# fm_receiver_schematic.net
KiCad netlist of a schematic drawn in EAGLE
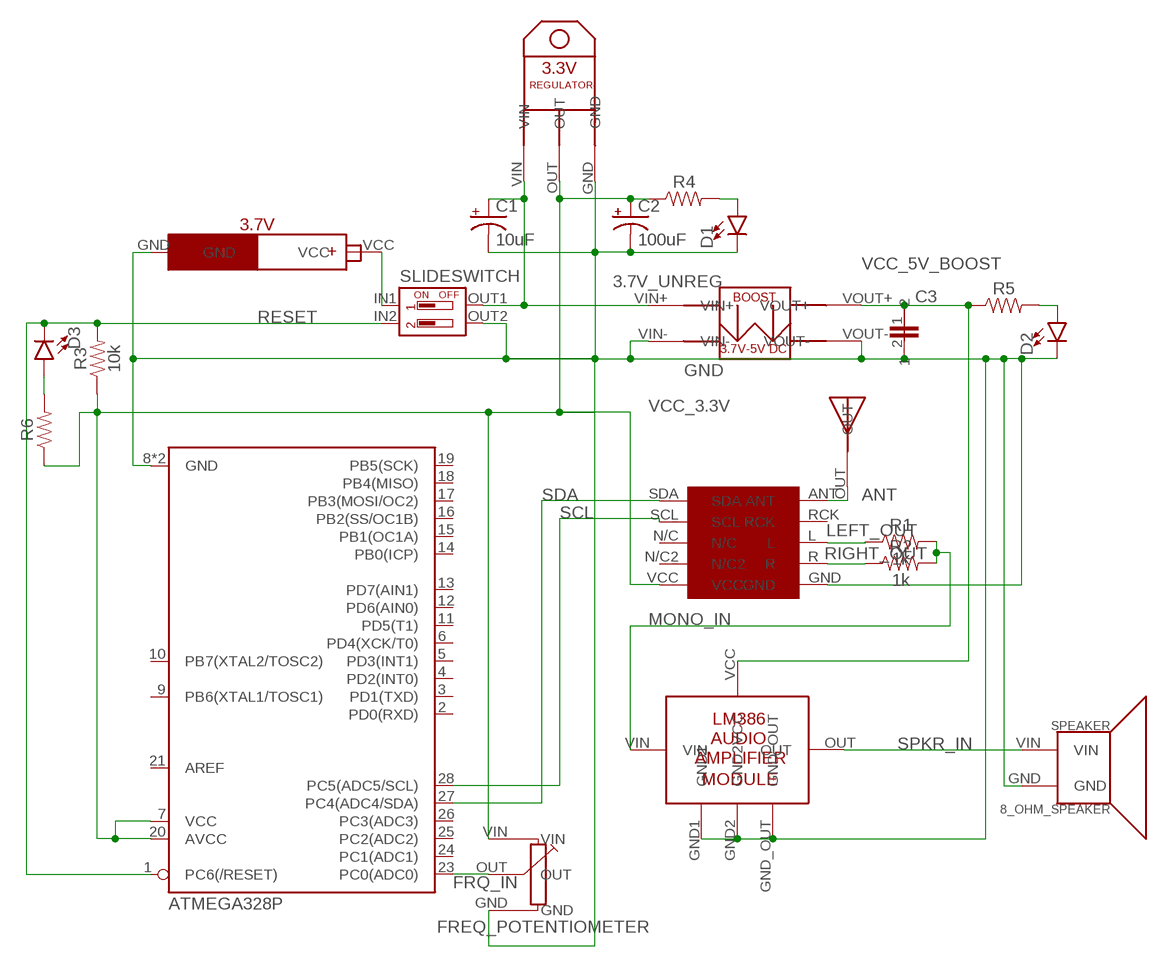
[diagram p0: schematic, sheet 1]

(export (version "E")
  (design (tool "Eeschema 10.0.6"))
  (components
    (comp (ref "3.3V_REGULATOR")
      (value "LDO_REG_3.3V")
      (footprint "eagle-import:LDO_REG_3.3V")
      (libsource (lib "eagle-import") (part "LDO_REG_3.3V"))
    )
    (comp (ref "3.7_5_BOOST")
      (value "3.7V_5V_BOOST_CONV")
      (footprint "eagle-import:3.7V_5V_BOOST_CONV")
      (libsource (lib "eagle-import") (part "3.7V_5V_BOOST_CONV"))
    )
    (comp (ref "ANTENNA")
      (value "SIMPLE_ANTENNA")
      (footprint "eagle-import:SIMPLE_ANTENNA")
      (libsource (lib "eagle-import") (part "SIMPLE_ANTENNA"))
    )
    (comp (ref "ATMEGA328P")
      (value "328P")
      (footprint "eagle-import:DIP28")
      (libsource (lib "eagle-import") (part "ATMEGA328P_PDIP"))
    )
    (comp (ref "C1")
      (value "10uF")
      (footprint "eagle-import:CPOL-RADIAL-2.5MM-5MM")
      (libsource (lib "eagle-import") (part "10UF-POLAR-RADIAL-2.5MM-25V-20%"))
    )
    (comp (ref "C2")
      (value "100uF")
      (footprint "eagle-import:CPOL-RADIAL-2.5MM-6.5MM")
      (libsource (lib "eagle-import") (part "100UF-POLAR-RADIAL-2.5MM-25V-20%"))
    )
    (comp (ref "C3")
      (value "0.1UF_CER_CAP")
      (footprint "eagle-import:0.1UF_CER_CAP")
      (libsource (lib "eagle-import") (part "0.1UF_CER_CAP"))
    )
    (comp (ref "D1")
      (value "LED5MM")
      (footprint "eagle-import:LED_5MM")
      (libsource (lib "eagle-import") (part "LED5MM"))
    )
    (comp (ref "D2")
      (value "LED5MM")
      (footprint "eagle-import:LED_5MM")
      (libsource (lib "eagle-import") (part "LED5MM"))
    )
    (comp (ref "D3")
      (value "LED5MM")
      (footprint "eagle-import:LED_5MM")
      (libsource (lib "eagle-import") (part "LED5MM"))
    )
    (comp (ref "FM_RECEIVER")
      (value "RDA")
      (footprint "eagle-import:RDA")
      (libsource (lib "eagle-import") (part "RDA"))
    )
    (comp (ref "FREQ_POTENTIOMETER")
      (value "POTENTIOMETER_LARGE")
      (footprint "eagle-import:POTENTIOMETER_LARGE")
      (libsource (lib "eagle-import") (part "POTENTIOMETER_LARGE"))
    )
    (comp (ref "LM386_MODULE")
      (value "LM386_AUDIO_AMP_MODULE")
      (footprint "eagle-import:LM386_AUDIO_AMP_MODULE")
      (libsource (lib "eagle-import") (part "LM386_AUDIO_AMP_MODULE"))
    )
    (comp (ref "PWR_SUPPLY")
      (value "3.7V_PWR_DESIGNATOR")
      (footprint "eagle-import:3.7V_PWR_DESIGNATOR")
      (libsource (lib "eagle-import") (part "3.7V_PWR_DESIGNATOR"))
    )
    (comp (ref "R1")
      (value "1k")
      (footprint "eagle-import:AXIAL-0.3")
      (libsource (lib "eagle-import") (part "1KOHM-HORIZ-1/4W-1%"))
    )
    (comp (ref "R2")
      (value "1k")
      (footprint "eagle-import:AXIAL-0.3")
      (libsource (lib "eagle-import") (part "1KOHM-HORIZ-1/4W-1%"))
    )
    (comp (ref "R3")
      (value "10k")
      (footprint "eagle-import:AXIAL-0.3")
      (libsource (lib "eagle-import") (part "10KOHM-HORIZ-1/4W-1%"))
    )
    (comp (ref "R4")
      (value "RESISTORAXIAL-0.3")
      (footprint "eagle-import:AXIAL-0.3")
      (libsource (lib "eagle-import") (part "RESISTORAXIAL-0.3"))
    )
    (comp (ref "R5")
      (value "RESISTORAXIAL-0.3")
      (footprint "eagle-import:AXIAL-0.3")
      (libsource (lib "eagle-import") (part "RESISTORAXIAL-0.3"))
    )
    (comp (ref "R6")
      (value "RESISTORAXIAL-0.3")
      (footprint "eagle-import:AXIAL-0.3")
      (libsource (lib "eagle-import") (part "RESISTORAXIAL-0.3"))
    )
    (comp (ref "SLIDESWITCH")
      (value "2_WAY_DIP_PWR_RST_SLIDESWITCH")
      (footprint "eagle-import:2_WAY_DIP_PWR_RST_SLIDESWITCH")
      (libsource (lib "eagle-import") (part "2_WAY_DIP_PWR_RST_SLIDESWITCH"))
    )
    (comp (ref "SPEAKER")
      (value "8_OHM_SPEAKER")
      (footprint "eagle-import:8_OHM_SPEAKER")
      (libsource (lib "eagle-import") (part "8_OHM_SPEAKER"))
    )
  )
  (nets
    (net (code "1") (name "/3.7V_UNREG") (class "Default")
      (node (ref "3.3V_REGULATOR") (pin "VIN") (pinfunction "VIN_VIN") (pintype "bidirectional"))
      (node (ref "3.7_5_BOOST") (pin "VIN+") (pinfunction "VIN+_VIN+") (pintype "bidirectional"))
      (node (ref "C1") (pin "1") (pinfunction "+_1") (pintype "passive"))
      (node (ref "SLIDESWITCH") (pin "OUT1") (pinfunction "OUT1_OUT1") (pintype "bidirectional"))
    )
    (net (code "2") (name "/ANT") (class "Default")
      (node (ref "ANTENNA") (pin "OUT") (pinfunction "OUT_OUT") (pintype "bidirectional"))
      (node (ref "FM_RECEIVER") (pin "ANT") (pinfunction "ANT_ANT") (pintype "input"))
    )
    (net (code "3") (name "/FRQ_IN") (class "Default")
      (node (ref "ATMEGA328P") (pin "23") (pinfunction "PC0(ADC0)_23") (pintype "bidirectional"))
      (node (ref "FREQ_POTENTIOMETER") (pin "OUT") (pinfunction "OUT_OUT") (pintype "bidirectional"))
    )
    (net (code "4") (name "/GND") (class "Default")
      (node (ref "3.3V_REGULATOR") (pin "GND") (pinfunction "GND_GND") (pintype "bidirectional"))
      (node (ref "3.7_5_BOOST") (pin "VIN-") (pinfunction "VIN-_VIN-") (pintype "bidirectional"))
      (node (ref "3.7_5_BOOST") (pin "VOUT-") (pinfunction "VOUT-_VOUT-") (pintype "bidirectional"))
      (node (ref "ATMEGA328P") (pin "22") (pinfunction "GND_22") (pintype "bidirectional"))
      (node (ref "ATMEGA328P") (pin "8") (pinfunction "GND_8") (pintype "bidirectional"))
      (node (ref "C1") (pin "2") (pinfunction "-_2") (pintype "passive"))
      (node (ref "C2") (pin "2") (pinfunction "-_2") (pintype "passive"))
      (node (ref "C3") (pin "2") (pinfunction "2_2") (pintype "bidirectional"))
      (node (ref "D1") (pin "K") (pinfunction "C_K") (pintype "passive"))
      (node (ref "D2") (pin "K") (pinfunction "C_K") (pintype "passive"))
      (node (ref "FM_RECEIVER") (pin "GND") (pinfunction "GND_GND") (pintype "power_in"))
      (node (ref "FREQ_POTENTIOMETER") (pin "GND") (pinfunction "GND_GND") (pintype "bidirectional"))
      (node (ref "LM386_MODULE") (pin "GND1") (pinfunction "GND1_GND1") (pintype "bidirectional"))
      (node (ref "LM386_MODULE") (pin "GND2") (pinfunction "GND2_GND2") (pintype "bidirectional"))
      (node (ref "LM386_MODULE") (pin "GND_OUT") (pinfunction "GND_OUT_GND_OUT") (pintype "bidirectional"))
      (node (ref "PWR_SUPPLY") (pin "GND") (pinfunction "GND_GND") (pintype "bidirectional"))
      (node (ref "SLIDESWITCH") (pin "OUT2") (pinfunction "OUT2_OUT2") (pintype "bidirectional"))
      (node (ref "SPEAKER") (pin "GND") (pinfunction "GND_GND") (pintype "bidirectional"))
    )
    (net (code "5") (name "/LEFT_OUT") (class "Default")
      (node (ref "FM_RECEIVER") (pin "L") (pinfunction "L_L") (pintype "output"))
      (node (ref "R1") (pin "P$1") (pinfunction "1_P$1") (pintype "passive"))
    )
    (net (code "6") (name "/MONO_IN") (class "Default")
      (node (ref "LM386_MODULE") (pin "VIN") (pinfunction "VIN_VIN") (pintype "bidirectional"))
      (node (ref "R1") (pin "P$2") (pinfunction "2_P$2") (pintype "passive"))
      (node (ref "R2") (pin "P$2") (pinfunction "2_P$2") (pintype "passive"))
    )
    (net (code "7") (name "/RESET") (class "Default")
      (node (ref "ATMEGA328P") (pin "1") (pinfunction "PC6(/RESET)_1") (pintype "bidirectional"))
      (node (ref "D3") (pin "K") (pinfunction "C_K") (pintype "passive"))
      (node (ref "R3") (pin "P$2") (pinfunction "2_P$2") (pintype "passive"))
      (node (ref "SLIDESWITCH") (pin "IN2") (pinfunction "IN2_IN2") (pintype "bidirectional"))
    )
    (net (code "8") (name "/RIGHT_OUT") (class "Default")
      (node (ref "FM_RECEIVER") (pin "R") (pinfunction "R_R") (pintype "output"))
      (node (ref "R2") (pin "P$1") (pinfunction "1_P$1") (pintype "passive"))
    )
    (net (code "9") (name "/SCL") (class "Default")
      (node (ref "ATMEGA328P") (pin "28") (pinfunction "PC5(ADC5/SCL)_28") (pintype "bidirectional"))
      (node (ref "FM_RECEIVER") (pin "SCL") (pinfunction "SCL_SCL") (pintype "bidirectional"))
    )
    (net (code "10") (name "/SDA") (class "Default")
      (node (ref "ATMEGA328P") (pin "27") (pinfunction "PC4(ADC4/SDA)_27") (pintype "bidirectional"))
      (node (ref "FM_RECEIVER") (pin "SDA") (pinfunction "SDA_SDA") (pintype "bidirectional"))
    )
    (net (code "11") (name "/SPKR_IN") (class "Default")
      (node (ref "LM386_MODULE") (pin "OUT") (pinfunction "OUT_OUT") (pintype "bidirectional"))
      (node (ref "SPEAKER") (pin "VIN") (pinfunction "VIN_VIN") (pintype "bidirectional"))
    )
    (net (code "12") (name "/VCC_3.3V") (class "Default")
      (node (ref "3.3V_REGULATOR") (pin "OUT") (pinfunction "OUT_OUT") (pintype "bidirectional"))
      (node (ref "ATMEGA328P") (pin "20") (pinfunction "AVCC_20") (pintype "bidirectional"))
      (node (ref "ATMEGA328P") (pin "7") (pinfunction "VCC_7") (pintype "bidirectional"))
      (node (ref "C2") (pin "1") (pinfunction "+_1") (pintype "passive"))
      (node (ref "FM_RECEIVER") (pin "VCC") (pinfunction "VCC_VCC") (pintype "power_in"))
      (node (ref "FREQ_POTENTIOMETER") (pin "VIN") (pinfunction "VIN_VIN") (pintype "bidirectional"))
      (node (ref "R3") (pin "P$1") (pinfunction "1_P$1") (pintype "passive"))
      (node (ref "R4") (pin "P$1") (pinfunction "1_P$1") (pintype "passive"))
      (node (ref "R6") (pin "P$1") (pinfunction "1_P$1") (pintype "passive"))
    )
    (net (code "13") (name "/VCC_5V_BOOST") (class "Default")
      (node (ref "3.7_5_BOOST") (pin "VOUT+") (pinfunction "VOUT+_VOUT+") (pintype "bidirectional"))
      (node (ref "C3") (pin "1") (pinfunction "1_1") (pintype "bidirectional"))
      (node (ref "LM386_MODULE") (pin "VCC") (pinfunction "VCC_VCC") (pintype "bidirectional"))
      (node (ref "R5") (pin "P$1") (pinfunction "1_P$1") (pintype "passive"))
    )
    (net (code "14") (name "Net-(PWR_SUPPLY-PadVCC)") (class "Default")
      (node (ref "PWR_SUPPLY") (pin "VCC") (pinfunction "VCC_VCC") (pintype "bidirectional"))
      (node (ref "SLIDESWITCH") (pin "IN1") (pinfunction "IN1_IN1") (pintype "bidirectional"))
    )
    (net (code "15") (name "Net-(R4-2)") (class "Default")
      (node (ref "D1") (pin "A") (pinfunction "A_A") (pintype "passive"))
      (node (ref "R4") (pin "P$2") (pinfunction "2_P$2") (pintype "passive"))
    )
    (net (code "16") (name "Net-(R5-2)") (class "Default")
      (node (ref "D2") (pin "A") (pinfunction "A_A") (pintype "passive"))
      (node (ref "R5") (pin "P$2") (pinfunction "2_P$2") (pintype "passive"))
    )
    (net (code "17") (name "Net-(R6-2)") (class "Default")
      (node (ref "D3") (pin "A") (pinfunction "A_A") (pintype "passive"))
      (node (ref "R6") (pin "P$2") (pinfunction "2_P$2") (pintype "passive"))
    )
    (net (code "18") (name "unconnected-(ATMEGA328P-AREF-Pad21)") (class "Default")
      (node (ref "ATMEGA328P") (pin "21") (pinfunction "AREF_21") (pintype "bidirectional"))
    )
    (net (code "19") (name "unconnected-(ATMEGA328P-PB0(ICP)-Pad14)") (class "Default")
      (node (ref "ATMEGA328P") (pin "14") (pinfunction "PB0(ICP)_14") (pintype "bidirectional"))
    )
    (net (code "20") (name "unconnected-(ATMEGA328P-PB1(OC1A)-Pad15)") (class "Default")
      (node (ref "ATMEGA328P") (pin "15") (pinfunction "PB1(OC1A)_15") (pintype "bidirectional"))
    )
    (net (code "21") (name "unconnected-(ATMEGA328P-PB2(SS{slash}OC1B)-Pad16)") (class "Default")
      (node (ref "ATMEGA328P") (pin "16") (pinfunction "PB2(SS/OC1B)_16") (pintype "bidirectional"))
    )
    (net (code "22") (name "unconnected-(ATMEGA328P-PB3(MOSI{slash}OC2)-Pad17)") (class "Default")
      (node (ref "ATMEGA328P") (pin "17") (pinfunction "PB3(MOSI/OC2)_17") (pintype "bidirectional"))
    )
    (net (code "23") (name "unconnected-(ATMEGA328P-PB4(MISO)-Pad18)") (class "Default")
      (node (ref "ATMEGA328P") (pin "18") (pinfunction "PB4(MISO)_18") (pintype "bidirectional"))
    )
    (net (code "24") (name "unconnected-(ATMEGA328P-PB5(SCK)-Pad19)") (class "Default")
      (node (ref "ATMEGA328P") (pin "19") (pinfunction "PB5(SCK)_19") (pintype "bidirectional"))
    )
    (net (code "25") (name "unconnected-(ATMEGA328P-PB6(XTAL1{slash}TOSC1)-Pad9)") (class "Default")
      (node (ref "ATMEGA328P") (pin "9") (pinfunction "PB6(XTAL1/TOSC1)_9") (pintype "bidirectional"))
    )
    (net (code "26") (name "unconnected-(ATMEGA328P-PB7(XTAL2{slash}TOSC2)-Pad10)") (class "Default")
      (node (ref "ATMEGA328P") (pin "10") (pinfunction "PB7(XTAL2/TOSC2)_10") (pintype "bidirectional"))
    )
    (net (code "27") (name "unconnected-(ATMEGA328P-PC1(ADC1)-Pad24)") (class "Default")
      (node (ref "ATMEGA328P") (pin "24") (pinfunction "PC1(ADC1)_24") (pintype "bidirectional"))
    )
    (net (code "28") (name "unconnected-(ATMEGA328P-PC2(ADC2)-Pad25)") (class "Default")
      (node (ref "ATMEGA328P") (pin "25") (pinfunction "PC2(ADC2)_25") (pintype "bidirectional"))
    )
    (net (code "29") (name "unconnected-(ATMEGA328P-PC3(ADC3)-Pad26)") (class "Default")
      (node (ref "ATMEGA328P") (pin "26") (pinfunction "PC3(ADC3)_26") (pintype "bidirectional"))
    )
    (net (code "30") (name "unconnected-(ATMEGA328P-PD0(RXD)-Pad2)") (class "Default")
      (node (ref "ATMEGA328P") (pin "2") (pinfunction "PD0(RXD)_2") (pintype "bidirectional"))
    )
    (net (code "31") (name "unconnected-(ATMEGA328P-PD1(TXD)-Pad3)") (class "Default")
      (node (ref "ATMEGA328P") (pin "3") (pinfunction "PD1(TXD)_3") (pintype "bidirectional"))
    )
    (net (code "32") (name "unconnected-(ATMEGA328P-PD2(INT0)-Pad4)") (class "Default")
      (node (ref "ATMEGA328P") (pin "4") (pinfunction "PD2(INT0)_4") (pintype "bidirectional"))
    )
    (net (code "33") (name "unconnected-(ATMEGA328P-PD3(INT1)-Pad5)") (class "Default")
      (node (ref "ATMEGA328P") (pin "5") (pinfunction "PD3(INT1)_5") (pintype "bidirectional"))
    )
    (net (code "34") (name "unconnected-(ATMEGA328P-PD4(XCK{slash}T0)-Pad6)") (class "Default")
      (node (ref "ATMEGA328P") (pin "6") (pinfunction "PD4(XCK/T0)_6") (pintype "bidirectional"))
    )
    (net (code "35") (name "unconnected-(ATMEGA328P-PD5(T1)-Pad11)") (class "Default")
      (node (ref "ATMEGA328P") (pin "11") (pinfunction "PD5(T1)_11") (pintype "bidirectional"))
    )
    (net (code "36") (name "unconnected-(ATMEGA328P-PD6(AIN0)-Pad12)") (class "Default")
      (node (ref "ATMEGA328P") (pin "12") (pinfunction "PD6(AIN0)_12") (pintype "bidirectional"))
    )
    (net (code "37") (name "unconnected-(ATMEGA328P-PD7(AIN1)-Pad13)") (class "Default")
      (node (ref "ATMEGA328P") (pin "13") (pinfunction "PD7(AIN1)_13") (pintype "bidirectional"))
    )
    (net (code "38") (name "unconnected-(FM_RECEIVER-PadN{slash}C)") (class "Default")
      (node (ref "FM_RECEIVER") (pin "N/C") (pinfunction "N/C_N/C") (pintype "passive"))
    )
    (net (code "39") (name "unconnected-(FM_RECEIVER-PadN{slash}C2)") (class "Default")
      (node (ref "FM_RECEIVER") (pin "N/C2") (pinfunction "N/C2_N/C2") (pintype "passive"))
    )
    (net (code "40") (name "unconnected-(FM_RECEIVER-PadRCK)") (class "Default")
      (node (ref "FM_RECEIVER") (pin "RCK") (pinfunction "RCK_RCK") (pintype "bidirectional"))
    )
  )
)
